# IMTM-SCH02.net
KiCad netlist of a schematic drawn in Altium Designer
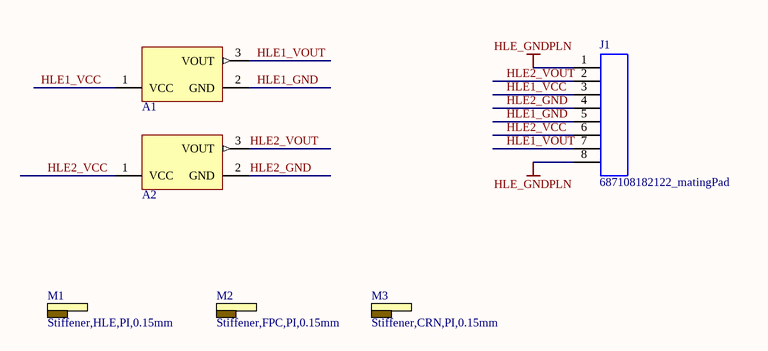
[diagram p0: IMTM-SCH02.SchDoc]

(export (version "E")
  (design (tool "Eeschema 10.0.6"))
  (components
    (comp (ref "A1")
      (value "A1324LUA-T")
      (footprint "A1324LUA-T")
      (description "ALLEGRO MICROSYSTEMS - A1324LUA-T - Hall Effect Sensor, Linear, 10 mA, SIP, 3 Pins, 4.5 V, 5.5 V")
      (fields (field (name "MANUFACTURER") "Allegro MicroSystems"))
      (libsource (lib "Schlib") (part "A1324LUA-T"))
    )
    (comp (ref "A2")
      (value "A1324LUA-T")
      (footprint "A1324LUA-T")
      (description "ALLEGRO MICROSYSTEMS - A1324LUA-T - Hall Effect Sensor, Linear, 10 mA, SIP, 3 Pins, 4.5 V, 5.5 V")
      (fields (field (name "MANUFACTURER") "Allegro MicroSystems"))
      (libsource (lib "Schlib") (part "A1324LUA-T"))
    )
    (comp (ref "J1")
      (value "687108182122_matingPad")
      (footprint "687108182122_MATINGPAD")
      (libsource (lib "Schlib") (part "687108182122_matingPad"))
    )
    (comp (ref "M1")
      (value "Stiffener,HLE,PI,0.15mm")
      (footprint "HLE_stiffener")
      (description "MECH,Stiffener,IMTM-PCB03_04,HLE")
      (fields (field (name "CREATEDBY") "A. Hadi"))
      (libsource (lib "Schlib") (part "HLE_STIFFENER"))
    )
    (comp (ref "M2")
      (value "Stiffener,FPC,PI,0.15mm")
      (footprint "FPC_STIFFENER")
      (description "MECH,Stiffener,IMTM-PCB03_04,FPC")
      (fields (field (name "CREATEDBY") "A. Hadi"))
      (libsource (lib "Schlib") (part "FPC_STIFFENER"))
    )
    (comp (ref "M3")
      (value "Stiffener,CRN,PI,0.15mm")
      (footprint "FPC_STIFFENER")
      (description "MECH,Stiffener,IMTM-PCB03_04,FPC")
      (fields (field (name "CREATEDBY") "A. Hadi"))
      (libsource (lib "Schlib") (part "FPC_STIFFENER"))
    )
  )
  (nets
    (net (code "1") (name "/HLE1_GND") (class "Default")
      (node (ref "A1") (pin "2") (pinfunction "GND_2") (pintype "power_in"))
      (node (ref "J1") (pin "5") (pinfunction "5_5") (pintype "passive"))
    )
    (net (code "2") (name "/HLE1_VCC") (class "Default")
      (node (ref "A1") (pin "1") (pinfunction "VCC_1") (pintype "power_in"))
      (node (ref "J1") (pin "3") (pinfunction "3_3") (pintype "passive"))
    )
    (net (code "3") (name "/HLE1_VOUT") (class "Default")
      (node (ref "A1") (pin "3") (pinfunction "VOUT_3") (pintype "output"))
      (node (ref "J1") (pin "7") (pinfunction "7_7") (pintype "passive"))
    )
    (net (code "4") (name "/HLE2_GND") (class "Default")
      (node (ref "A2") (pin "2") (pinfunction "GND_2") (pintype "power_in"))
      (node (ref "J1") (pin "4") (pinfunction "4_4") (pintype "passive"))
    )
    (net (code "5") (name "/HLE2_VCC") (class "Default")
      (node (ref "A2") (pin "1") (pinfunction "VCC_1") (pintype "power_in"))
      (node (ref "J1") (pin "6") (pinfunction "6_6") (pintype "passive"))
    )
    (net (code "6") (name "/HLE2_VOUT") (class "Default")
      (node (ref "A2") (pin "3") (pinfunction "VOUT_3") (pintype "output"))
      (node (ref "J1") (pin "2") (pinfunction "2_2") (pintype "passive"))
    )
    (net (code "7") (name "HLE_GNDPLN") (class "Default")
      (node (ref "J1") (pin "1") (pinfunction "1_1") (pintype "passive"))
      (node (ref "J1") (pin "8") (pinfunction "8_8") (pintype "passive"))
    )
  )
)
